# Stethoscope_v1_0.net
KiCad netlist of a schematic drawn in EAGLE
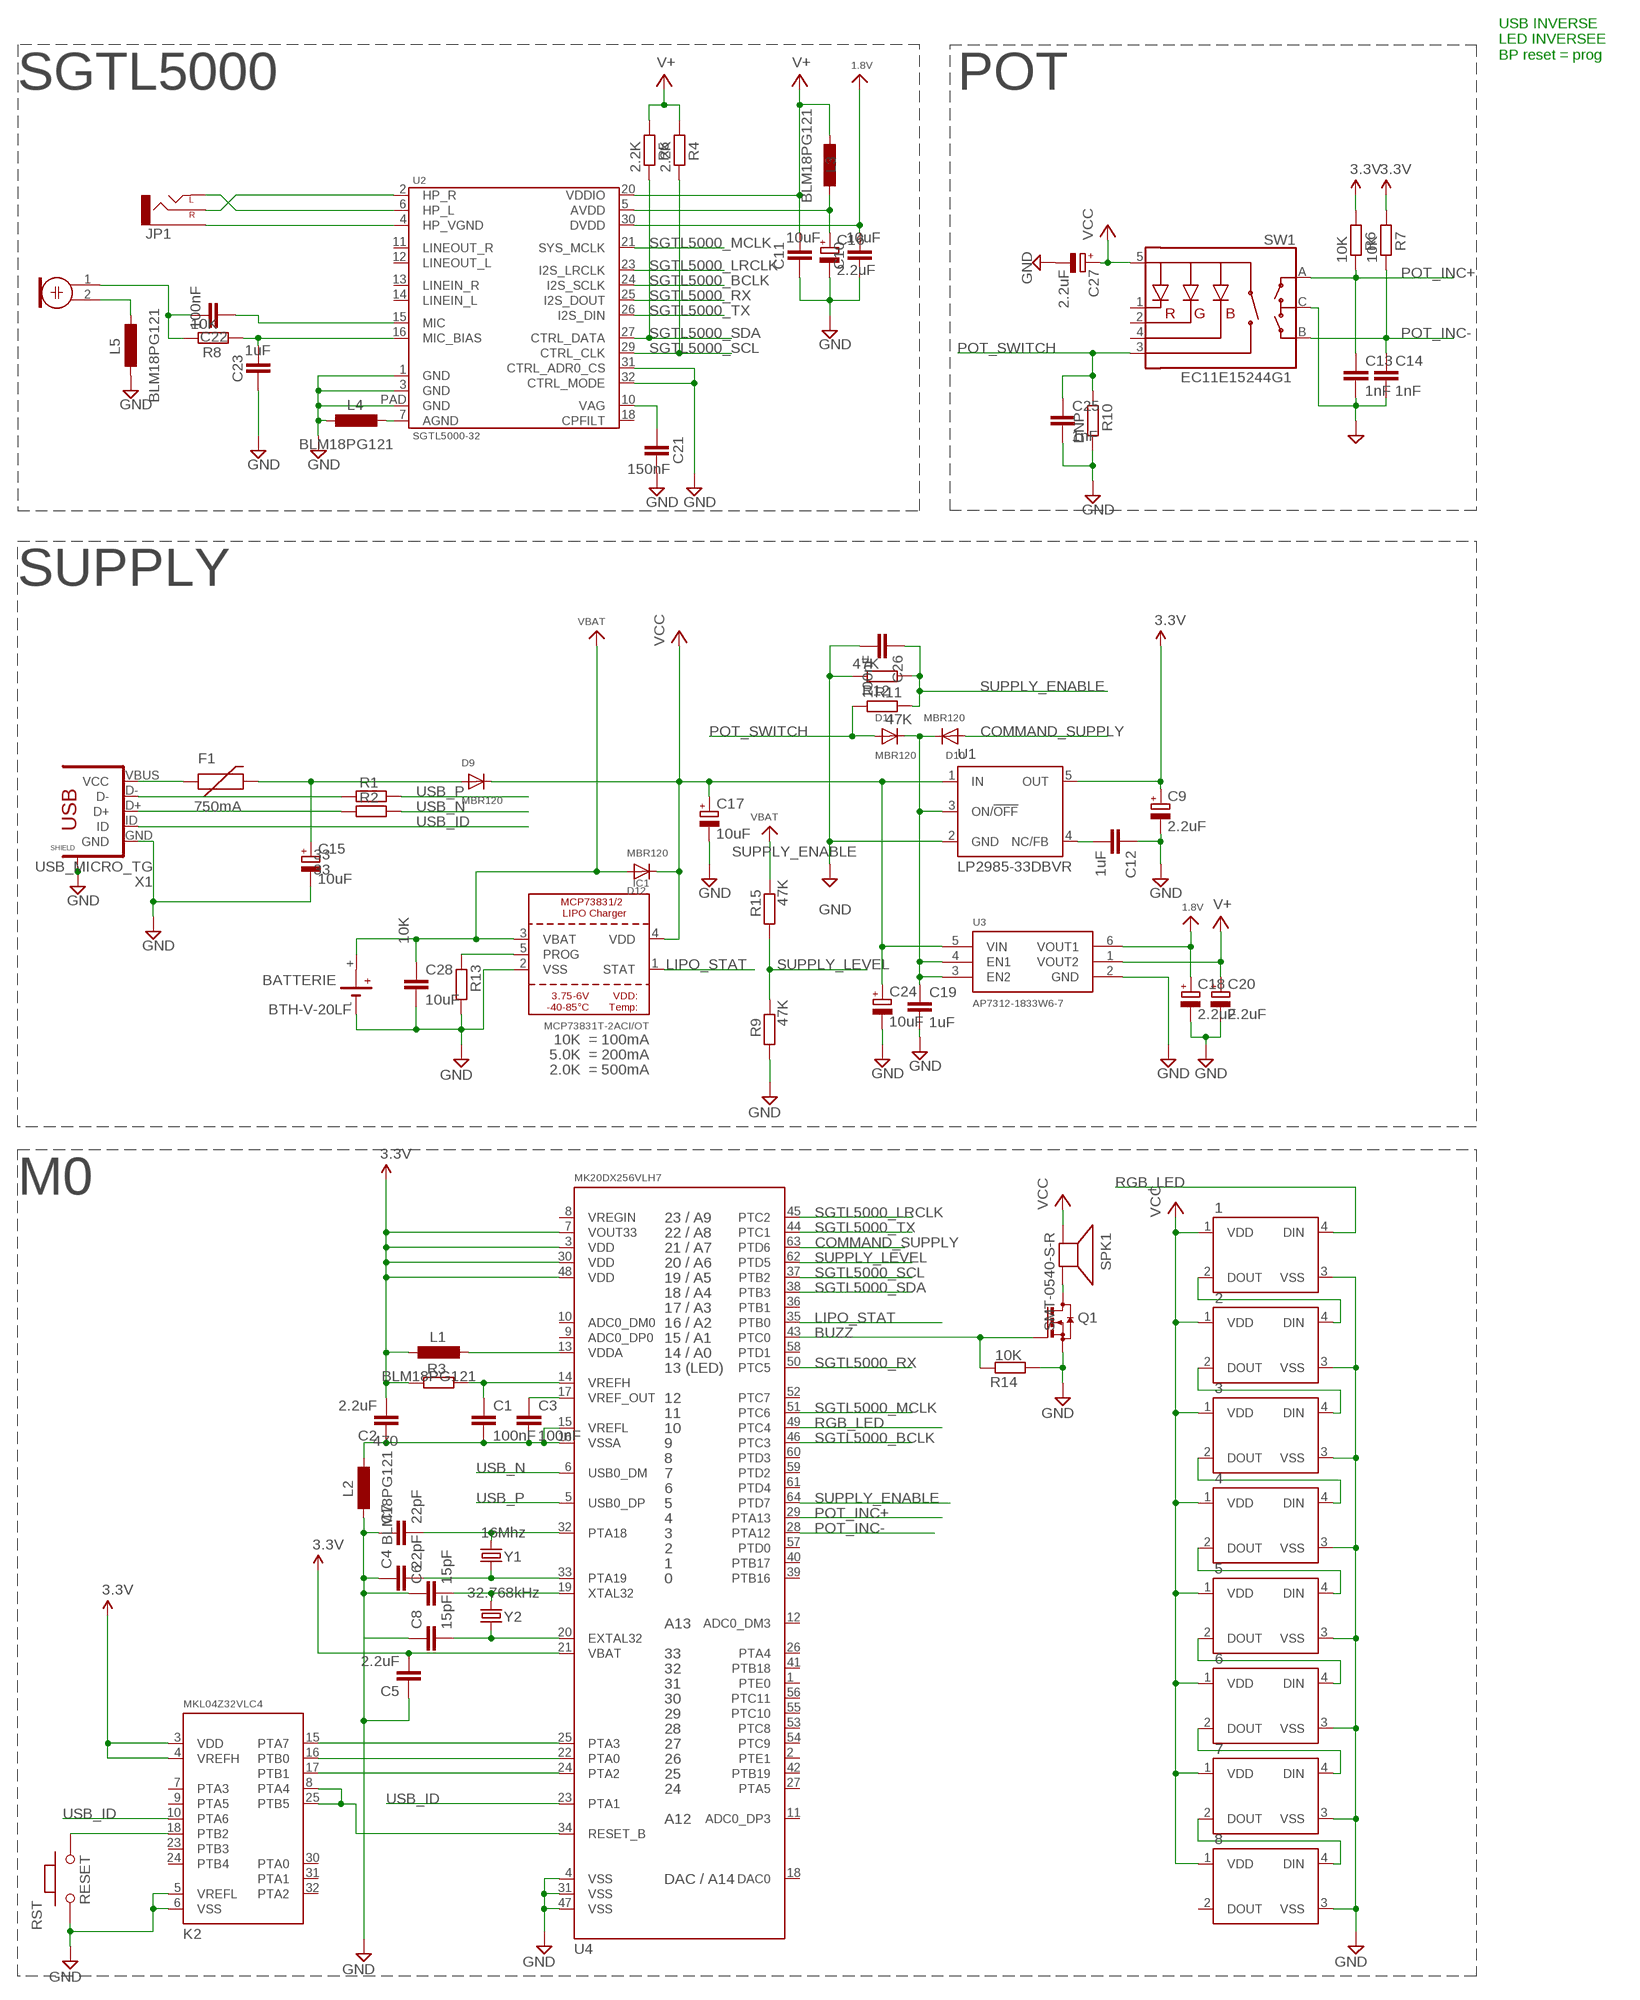
[diagram p0: schematic, sheet 1]

(export (version "E")
  (design (tool "Eeschema 10.0.6"))
  (components
    (comp (ref "1")
      (value "WS2812B")
      (footprint "eagle-import:WS2812B")
      (libsource (lib "eagle-import") (part "WS2812B"))
    )
    (comp (ref "2")
      (value "WS2812B")
      (footprint "eagle-import:WS2812B")
      (libsource (lib "eagle-import") (part "WS2812B"))
    )
    (comp (ref "3")
      (value "WS2812B")
      (footprint "eagle-import:WS2812B")
      (libsource (lib "eagle-import") (part "WS2812B"))
    )
    (comp (ref "4")
      (value "WS2812B")
      (footprint "eagle-import:WS2812B")
      (libsource (lib "eagle-import") (part "WS2812B"))
    )
    (comp (ref "5")
      (value "WS2812B")
      (footprint "eagle-import:WS2812B")
      (libsource (lib "eagle-import") (part "WS2812B"))
    )
    (comp (ref "6")
      (value "WS2812B")
      (footprint "eagle-import:WS2812B")
      (libsource (lib "eagle-import") (part "WS2812B"))
    )
    (comp (ref "7")
      (value "WS2812B")
      (footprint "eagle-import:WS2812B")
      (libsource (lib "eagle-import") (part "WS2812B"))
    )
    (comp (ref "8")
      (value "WS2812B")
      (footprint "eagle-import:WS2812B")
      (libsource (lib "eagle-import") (part "WS2812B"))
    )
    (comp (ref "BATTERIE")
      (value "BTH-V-20LF")
      (footprint "eagle-import:3V_BAT_HOLDER")
      (libsource (lib "eagle-import") (part "B1"))
    )
    (comp (ref "C1")
      (value "100nF")
      (footprint "eagle-import:C0603")
      (libsource (lib "eagle-import") (part "C-EUC0603"))
    )
    (comp (ref "C2")
      (value "2.2uF")
      (footprint "eagle-import:C0603")
      (libsource (lib "eagle-import") (part "C-EUC0603"))
    )
    (comp (ref "C3")
      (value "100nF")
      (footprint "eagle-import:C0603")
      (libsource (lib "eagle-import") (part "C-EUC0603"))
    )
    (comp (ref "C4")
      (value "22pF")
      (footprint "eagle-import:C0603")
      (libsource (lib "eagle-import") (part "C-EUC0603"))
    )
    (comp (ref "C5")
      (value "2.2uF")
      (footprint "eagle-import:C0603")
      (libsource (lib "eagle-import") (part "C-EUC0603"))
    )
    (comp (ref "C6")
      (value "15pF")
      (footprint "eagle-import:C0603")
      (libsource (lib "eagle-import") (part "C-EUC0603"))
    )
    (comp (ref "C7")
      (value "22pF")
      (footprint "eagle-import:C0603")
      (libsource (lib "eagle-import") (part "C-EUC0603"))
    )
    (comp (ref "C8")
      (value "15pF")
      (footprint "eagle-import:C0603")
      (libsource (lib "eagle-import") (part "C-EUC0603"))
    )
    (comp (ref "C9")
      (value "2.2uF")
      (footprint "eagle-import:C0805POL")
      (libsource (lib "eagle-import") (part "CPOL-EUC0805POL"))
    )
    (comp (ref "C10")
      (value "10uF")
      (footprint "eagle-import:C0805")
      (libsource (lib "eagle-import") (part "C-EUC0805"))
    )
    (comp (ref "C11")
      (value "10uF")
      (footprint "eagle-import:C0805")
      (libsource (lib "eagle-import") (part "C-EUC0805"))
    )
    (comp (ref "C12")
      (value "1uF")
      (footprint "eagle-import:C0603")
      (libsource (lib "eagle-import") (part "C-EUC0603"))
    )
    (comp (ref "C13")
      (value "1nF")
      (footprint "eagle-import:C0603")
      (libsource (lib "eagle-import") (part "C-EUC0603"))
    )
    (comp (ref "C14")
      (value "1nF")
      (footprint "eagle-import:C0603")
      (libsource (lib "eagle-import") (part "C-EUC0603"))
    )
    (comp (ref "C15")
      (value "10uF")
      (footprint "eagle-import:C0805POL")
      (libsource (lib "eagle-import") (part "CPOL-EUC0805POL"))
    )
    (comp (ref "C16")
      (value "2.2uF")
      (footprint "eagle-import:C0805POL")
      (libsource (lib "eagle-import") (part "CPOL-EUC0805POL"))
    )
    (comp (ref "C17")
      (value "10uF")
      (footprint "eagle-import:C0805POL")
      (libsource (lib "eagle-import") (part "CPOL-EUC0805POL"))
    )
    (comp (ref "C18")
      (value "2.2uF")
      (footprint "eagle-import:C0805POL")
      (libsource (lib "eagle-import") (part "CPOL-EUC0805POL"))
    )
    (comp (ref "C19")
      (value "1uF")
      (footprint "eagle-import:C0603")
      (libsource (lib "eagle-import") (part "C-EUC0603"))
    )
    (comp (ref "C20")
      (value "2.2uF")
      (footprint "eagle-import:C0805POL")
      (libsource (lib "eagle-import") (part "CPOL-EUC0805POL"))
    )
    (comp (ref "C21")
      (value "150nF")
      (footprint "eagle-import:C0805")
      (libsource (lib "eagle-import") (part "C-EUC0805"))
    )
    (comp (ref "C22")
      (value "100nF")
      (footprint "eagle-import:C0805")
      (libsource (lib "eagle-import") (part "C-EUC0805"))
    )
    (comp (ref "C23")
      (value "1uF")
      (footprint "eagle-import:C0805")
      (libsource (lib "eagle-import") (part "C-EUC0805"))
    )
    (comp (ref "C24")
      (value "10uF")
      (footprint "eagle-import:C0805POL")
      (libsource (lib "eagle-import") (part "CPOL-EUC0805POL"))
    )
    (comp (ref "C25")
      (value "1nF")
      (footprint "eagle-import:C0603")
      (libsource (lib "eagle-import") (part "C-EUC0603"))
    )
    (comp (ref "C26")
      (value "100nF")
      (footprint "eagle-import:C0603")
      (libsource (lib "eagle-import") (part "C-EUC0603"))
    )
    (comp (ref "C27")
      (value "2.2uF")
      (footprint "eagle-import:C0805POL")
      (libsource (lib "eagle-import") (part "CPOL-EUC0805POL"))
    )
    (comp (ref "C28")
      (value "10uF")
      (footprint "eagle-import:C1206")
      (libsource (lib "eagle-import") (part "resistor_C-EUC1206"))
    )
    (comp (ref "D9")
      (value "MBR120")
      (footprint "eagle-import:SOD-323F")
      (libsource (lib "eagle-import") (part "DIODESOD-323F"))
    )
    (comp (ref "D10")
      (value "MBR120")
      (footprint "eagle-import:SOD-323F")
      (libsource (lib "eagle-import") (part "DIODESOD-323F"))
    )
    (comp (ref "D11")
      (value "MBR120")
      (footprint "eagle-import:SOD-323F")
      (libsource (lib "eagle-import") (part "DIODESOD-323F"))
    )
    (comp (ref "D12")
      (value "MBR120")
      (footprint "eagle-import:SOD-323F")
      (libsource (lib "eagle-import") (part "DIODESOD-323F"))
    )
    (comp (ref "F1")
      (value "750mA")
      (footprint "eagle-import:0603")
      (libsource (lib "eagle-import") (part "PTC0603"))
    )
    (comp (ref "IC1")
      (value "MCP73831T-2ACI/OT")
      (footprint "eagle-import:SOT23-5")
      (libsource (lib "eagle-import") (part "MCP73831/2"))
    )
    (comp (ref "JP1")
      (value "AUDIO-JACK1:1")
      (footprint "eagle-import:STEREOJACK2.5MM")
      (libsource (lib "eagle-import") (part "AUDIO-JACK1{colon}1"))
    )
    (comp (ref "K2")
      (value "MKL04Z32VLC4")
      (footprint "eagle-import:LQFP32-08")
      (fields (field (name "MF") "PJRC") (field (name "MPN") "IC_MKL04Z32_TQFP32"))
      (libsource (lib "eagle-import") (part "MKL04Z32VLC4"))
    )
    (comp (ref "L1")
      (value "BLM18PG121")
      (footprint "eagle-import:L0603")
      (libsource (lib "eagle-import") (part "L-EUL0603"))
    )
    (comp (ref "L2")
      (value "BLM18PG121")
      (footprint "eagle-import:L0603")
      (libsource (lib "eagle-import") (part "L-EUL0603"))
    )
    (comp (ref "L3")
      (value "BLM18PG121")
      (footprint "eagle-import:L0603")
      (libsource (lib "eagle-import") (part "L-EUL0603"))
    )
    (comp (ref "L4")
      (value "BLM18PG121")
      (footprint "eagle-import:L0603")
      (libsource (lib "eagle-import") (part "L-EUL0603"))
    )
    (comp (ref "L5")
      (value "BLM18PG121")
      (footprint "eagle-import:L0603")
      (libsource (lib "eagle-import") (part "L-EUL0603"))
    )
    (comp (ref "M1")
      (value "ELECTRET_MICROPHON-F6050AP")
      (footprint "eagle-import:F6050AP")
      (libsource (lib "eagle-import") (part "ELECTRET_MICROPHON-F6050AP"))
    )
    (comp (ref "Q1")
      (value "BSS123")
      (footprint "eagle-import:SOT23")
      (libsource (lib "eagle-import") (part "BSS123"))
    )
    (comp (ref "R1")
      (value "33")
      (footprint "eagle-import:R0603")
      (libsource (lib "eagle-import") (part "resistor_R-EU_R0603"))
    )
    (comp (ref "R2")
      (value "33")
      (footprint "eagle-import:R0603")
      (libsource (lib "eagle-import") (part "resistor_R-EU_R0603"))
    )
    (comp (ref "R3")
      (value "470")
      (footprint "eagle-import:R0603")
      (libsource (lib "eagle-import") (part "resistor_R-EU_R0603"))
    )
    (comp (ref "R4")
      (value "2.2K")
      (footprint "eagle-import:R0603")
      (libsource (lib "eagle-import") (part "R-EU_R0603"))
    )
    (comp (ref "R5")
      (value "2.2K")
      (footprint "eagle-import:R0603")
      (libsource (lib "eagle-import") (part "R-EU_R0603"))
    )
    (comp (ref "R6")
      (value "10K")
      (footprint "eagle-import:R0603")
      (libsource (lib "eagle-import") (part "R-EU_R0603"))
    )
    (comp (ref "R7")
      (value "10K")
      (footprint "eagle-import:R0603")
      (libsource (lib "eagle-import") (part "R-EU_R0603"))
    )
    (comp (ref "R8")
      (value "10K")
      (footprint "eagle-import:R0603")
      (libsource (lib "eagle-import") (part "R-EU_R0603"))
    )
    (comp (ref "R9")
      (value "47K")
      (footprint "eagle-import:R0603")
      (libsource (lib "eagle-import") (part "resistor_R-EU_R0603"))
    )
    (comp (ref "R10")
      (value "DNP")
      (footprint "eagle-import:R0603")
      (libsource (lib "eagle-import") (part "R-EU_R0603"))
    )
    (comp (ref "R11")
      (value "47K")
      (footprint "eagle-import:R0603")
      (libsource (lib "eagle-import") (part "resistor_R-EU_R0603"))
    )
    (comp (ref "R12")
      (value "47K")
      (footprint "eagle-import:R0603")
      (libsource (lib "eagle-import") (part "resistor_R-EU_R0603"))
    )
    (comp (ref "R13")
      (value "10K")
      (footprint "eagle-import:R0603")
      (libsource (lib "eagle-import") (part "resistor_R-EU_R0603"))
    )
    (comp (ref "R14")
      (value "10K")
      (footprint "eagle-import:R0603")
      (libsource (lib "eagle-import") (part "R-EU_R0603"))
    )
    (comp (ref "R15")
      (value "47K")
      (footprint "eagle-import:R0603")
      (libsource (lib "eagle-import") (part "resistor_R-EU_R0603"))
    )
    (comp (ref "RST")
      (value "RESET")
      (footprint "eagle-import:157SW")
      (libsource (lib "eagle-import") (part "PB157"))
    )
    (comp (ref "SPK1")
      (value "SMT-0540-S-R")
      (footprint "eagle-import:SMT-0540-S-R")
      (libsource (lib "eagle-import") (part "SMT-0540-S-R"))
    )
    (comp (ref "SW1")
      (value "EC11E15244G1")
      (footprint "eagle-import:ENCODER_LED_3_KIT")
      (libsource (lib "eagle-import") (part "ENCODER_RGB_CAKIT"))
    )
    (comp (ref "U1")
      (value "LP2985-33DBVR")
      (footprint "eagle-import:SOT23-DBV")
      (libsource (lib "eagle-import") (part "LP2985-XXDBVR33"))
    )
    (comp (ref "U2")
      (value "SGTL5000-32")
      (footprint "eagle-import:QFN-32-5MM")
      (libsource (lib "eagle-import") (part "SGTL5000-32"))
    )
    (comp (ref "U3")
      (value "AP7312-1833W6-7")
      (footprint "eagle-import:SOT23-6")
      (libsource (lib "eagle-import") (part "VREG_SOT23-6_DUALAP7312"))
    )
    (comp (ref "U4")
      (value "MK20DX256VLH7")
      (footprint "eagle-import:LQFP64-05")
      (fields (field (name "MF") "NXP"))
      (libsource (lib "eagle-import") (part "MK20DX256VLH7"))
    )
    (comp (ref "X1")
      (value "USB_MICRO_TG")
      (footprint "eagle-import:USB_MICRO_TG")
      (libsource (lib "eagle-import") (part "USB_MICRO_TG"))
    )
    (comp (ref "Y1")
      (value "16Mhz")
      (footprint "eagle-import:CRYSTAL-SMD-3.2X1.5MM")
      (libsource (lib "eagle-import") (part "CRYSTAL3.2X1.5MM"))
    )
    (comp (ref "Y2")
      (value "32.768kHz")
      (footprint "eagle-import:CRYSTAL-SMD-3.2X1.5MM")
      (libsource (lib "eagle-import") (part "CRYSTAL3.2X1.5MM"))
    )
  )
  (nets
    (net (code "1") (name "/BUZZ") (class "Default")
      (node (ref "Q1") (pin "1") (pinfunction "G_1") (pintype "passive"))
      (node (ref "R14") (pin "2") (pinfunction "2_2") (pintype "passive"))
      (node (ref "U4") (pin "43") (pinfunction "PTC0_43") (pintype "bidirectional"))
    )
    (net (code "2") (name "/COMMAND_SUPPLY") (class "Default")
      (node (ref "D10") (pin "A") (pinfunction "A_A") (pintype "passive"))
      (node (ref "U4") (pin "63") (pinfunction "PTD6_63") (pintype "bidirectional"))
    )
    (net (code "3") (name "/LIPO_STAT") (class "Default")
      (node (ref "IC1") (pin "1") (pinfunction "STAT_1") (pintype "output"))
      (node (ref "U4") (pin "35") (pinfunction "PTB0_35") (pintype "bidirectional"))
    )
    (net (code "4") (name "/POT_INC+") (class "Default")
      (node (ref "C13") (pin "1") (pinfunction "1_1") (pintype "passive"))
      (node (ref "R6") (pin "1") (pinfunction "1_1") (pintype "passive"))
      (node (ref "SW1") (pin "A") (pinfunction "A_A") (pintype "bidirectional"))
      (node (ref "U4") (pin "29") (pinfunction "PTA13_29") (pintype "bidirectional"))
    )
    (net (code "5") (name "/POT_INC-") (class "Default")
      (node (ref "C14") (pin "1") (pinfunction "1_1") (pintype "passive"))
      (node (ref "R7") (pin "1") (pinfunction "1_1") (pintype "passive"))
      (node (ref "SW1") (pin "B") (pinfunction "B_B") (pintype "bidirectional"))
      (node (ref "U4") (pin "28") (pinfunction "PTA12_28") (pintype "bidirectional"))
    )
    (net (code "6") (name "/POT_SWITCH") (class "Default")
      (node (ref "C25") (pin "1") (pinfunction "1_1") (pintype "passive"))
      (node (ref "D11") (pin "A") (pinfunction "A_A") (pintype "passive"))
      (node (ref "R10") (pin "2") (pinfunction "2_2") (pintype "passive"))
      (node (ref "R11") (pin "1") (pinfunction "1_1") (pintype "passive"))
      (node (ref "SW1") (pin "3") (pinfunction "SW_3") (pintype "passive"))
    )
    (net (code "7") (name "/RGB_LED") (class "Default")
      (node (ref "1") (pin "4") (pinfunction "DIN_4") (pintype "input"))
      (node (ref "U4") (pin "49") (pinfunction "PTC4_49") (pintype "bidirectional"))
    )
    (net (code "8") (name "/SGTL5000_BCLK") (class "Default")
      (node (ref "U2") (pin "24") (pinfunction "I2S_SCLK_24") (pintype "bidirectional"))
      (node (ref "U4") (pin "46") (pinfunction "PTC3_46") (pintype "bidirectional"))
    )
    (net (code "9") (name "/SGTL5000_LRCLK") (class "Default")
      (node (ref "U2") (pin "23") (pinfunction "I2S_LRCLK_23") (pintype "bidirectional"))
      (node (ref "U4") (pin "45") (pinfunction "PTC2_45") (pintype "bidirectional"))
    )
    (net (code "10") (name "/SGTL5000_MCLK") (class "Default")
      (node (ref "U2") (pin "21") (pinfunction "SYS_MCLK_21") (pintype "bidirectional"))
      (node (ref "U4") (pin "51") (pinfunction "PTC6_51") (pintype "bidirectional"))
    )
    (net (code "11") (name "/SGTL5000_RX") (class "Default")
      (node (ref "U2") (pin "25") (pinfunction "I2S_DOUT_25") (pintype "bidirectional"))
      (node (ref "U4") (pin "50") (pinfunction "PTC5_50") (pintype "bidirectional"))
    )
    (net (code "12") (name "/SGTL5000_SCL") (class "Default")
      (node (ref "R4") (pin "1") (pinfunction "1_1") (pintype "passive"))
      (node (ref "U2") (pin "29") (pinfunction "CTRL_CLK_29") (pintype "bidirectional"))
      (node (ref "U4") (pin "37") (pinfunction "PTB2_37") (pintype "bidirectional"))
    )
    (net (code "13") (name "/SGTL5000_SDA") (class "Default")
      (node (ref "R5") (pin "1") (pinfunction "1_1") (pintype "passive"))
      (node (ref "U2") (pin "27") (pinfunction "CTRL_DATA_27") (pintype "bidirectional"))
      (node (ref "U4") (pin "38") (pinfunction "PTB3_38") (pintype "bidirectional"))
    )
    (net (code "14") (name "/SGTL5000_TX") (class "Default")
      (node (ref "U2") (pin "26") (pinfunction "I2S_DIN_26") (pintype "bidirectional"))
      (node (ref "U4") (pin "44") (pinfunction "PTC1_44") (pintype "bidirectional"))
    )
    (net (code "15") (name "/SUPPLY_ENABLE") (class "Default")
      (node (ref "C26") (pin "1") (pinfunction "1_1") (pintype "passive"))
      (node (ref "R11") (pin "2") (pinfunction "2_2") (pintype "passive"))
      (node (ref "R12") (pin "1") (pinfunction "1_1") (pintype "passive"))
      (node (ref "U4") (pin "64") (pinfunction "PTD7_64") (pintype "bidirectional"))
    )
    (net (code "16") (name "/SUPPLY_LEVEL") (class "Default")
      (node (ref "R15") (pin "1") (pinfunction "1_1") (pintype "passive"))
      (node (ref "R9") (pin "2") (pinfunction "2_2") (pintype "passive"))
      (node (ref "U4") (pin "62") (pinfunction "PTD5_62") (pintype "bidirectional"))
    )
    (net (code "17") (name "/USB_ID") (class "Default")
      (node (ref "K2") (pin "10") (pinfunction "PTA6_10") (pintype "bidirectional"))
      (node (ref "U4") (pin "23") (pinfunction "PTA1_23") (pintype "bidirectional"))
      (node (ref "X1") (pin "ID") (pinfunction "ID_ID") (pintype "bidirectional"))
    )
    (net (code "18") (name "/USB_N") (class "Default")
      (node (ref "R2") (pin "1") (pinfunction "1_1") (pintype "passive"))
      (node (ref "U4") (pin "6") (pinfunction "USB0_DM_6") (pintype "bidirectional"))
    )
    (net (code "19") (name "/USB_P") (class "Default")
      (node (ref "R1") (pin "1") (pinfunction "1_1") (pintype "passive"))
      (node (ref "U4") (pin "5") (pinfunction "USB0_DP_5") (pintype "bidirectional"))
    )
    (net (code "20") (name "1.8V") (class "Default")
      (node (ref "C10") (pin "2") (pinfunction "2_2") (pintype "passive"))
      (node (ref "C18") (pin "SMD+") (pinfunction "+_SMD+") (pintype "passive"))
      (node (ref "U2") (pin "30") (pinfunction "DVDD_30") (pintype "bidirectional"))
      (node (ref "U3") (pin "6") (pinfunction "VOUT1_6") (pintype "bidirectional"))
    )
    (net (code "21") (name "3.3V") (class "Default")
      (node (ref "C2") (pin "2") (pinfunction "2_2") (pintype "passive"))
      (node (ref "C5") (pin "2") (pinfunction "2_2") (pintype "passive"))
      (node (ref "C9") (pin "SMD+") (pinfunction "+_SMD+") (pintype "passive"))
      (node (ref "K2") (pin "3") (pinfunction "VDD_3") (pintype "bidirectional"))
      (node (ref "K2") (pin "4") (pinfunction "VREFH_4") (pintype "bidirectional"))
      (node (ref "L1") (pin "2") (pinfunction "2_2") (pintype "passive"))
      (node (ref "R3") (pin "2") (pinfunction "2_2") (pintype "passive"))
      (node (ref "R6") (pin "2") (pinfunction "2_2") (pintype "passive"))
      (node (ref "R7") (pin "2") (pinfunction "2_2") (pintype "passive"))
      (node (ref "U1") (pin "5") (pinfunction "OUT_5") (pintype "passive"))
      (node (ref "U4") (pin "21") (pinfunction "VBAT_21") (pintype "bidirectional"))
      (node (ref "U4") (pin "3") (pinfunction "VDD_3") (pintype "bidirectional"))
      (node (ref "U4") (pin "30") (pinfunction "VDD_30") (pintype "bidirectional"))
      (node (ref "U4") (pin "48") (pinfunction "VDD_48") (pintype "bidirectional"))
      (node (ref "U4") (pin "7") (pinfunction "VOUT33_7") (pintype "bidirectional"))
    )
    (net (code "22") (name "GND") (class "Default")
      (node (ref "1") (pin "3") (pinfunction "VSS_3") (pintype "power_in"))
      (node (ref "2") (pin "3") (pinfunction "VSS_3") (pintype "power_in"))
      (node (ref "3") (pin "3") (pinfunction "VSS_3") (pintype "power_in"))
      (node (ref "4") (pin "3") (pinfunction "VSS_3") (pintype "power_in"))
      (node (ref "5") (pin "3") (pinfunction "VSS_3") (pintype "power_in"))
      (node (ref "6") (pin "3") (pinfunction "VSS_3") (pintype "power_in"))
      (node (ref "7") (pin "3") (pinfunction "VSS_3") (pintype "power_in"))
      (node (ref "8") (pin "3") (pinfunction "VSS_3") (pintype "power_in"))
      (node (ref "BATTERIE") (pin "-") (pinfunction "-_-") (pintype "passive"))
      (node (ref "C10") (pin "1") (pinfunction "1_1") (pintype "passive"))
      (node (ref "C11") (pin "1") (pinfunction "1_1") (pintype "passive"))
      (node (ref "C12") (pin "1") (pinfunction "1_1") (pintype "passive"))
      (node (ref "C13") (pin "2") (pinfunction "2_2") (pintype "passive"))
      (node (ref "C14") (pin "2") (pinfunction "2_2") (pintype "passive"))
      (node (ref "C15") (pin "SMD-") (pinfunction "-_SMD-") (pintype "passive"))
      (node (ref "C16") (pin "SMD-") (pinfunction "-_SMD-") (pintype "passive"))
      (node (ref "C17") (pin "SMD-") (pinfunction "-_SMD-") (pintype "passive"))
      (node (ref "C18") (pin "SMD-") (pinfunction "-_SMD-") (pintype "passive"))
      (node (ref "C19") (pin "2") (pinfunction "2_2") (pintype "passive"))
      (node (ref "C20") (pin "SMD-") (pinfunction "-_SMD-") (pintype "passive"))
      (node (ref "C21") (pin "2") (pinfunction "2_2") (pintype "passive"))
      (node (ref "C23") (pin "1") (pinfunction "1_1") (pintype "passive"))
      (node (ref "C24") (pin "SMD-") (pinfunction "-_SMD-") (pintype "passive"))
      (node (ref "C25") (pin "2") (pinfunction "2_2") (pintype "passive"))
      (node (ref "C26") (pin "2") (pinfunction "2_2") (pintype "passive"))
      (node (ref "C27") (pin "SMD-") (pinfunction "-_SMD-") (pintype "passive"))
      (node (ref "C28") (pin "2") (pinfunction "2_2") (pintype "passive"))
      (node (ref "C4") (pin "1") (pinfunction "1_1") (pintype "passive"))
      (node (ref "C5") (pin "1") (pinfunction "1_1") (pintype "passive"))
      (node (ref "C6") (pin "1") (pinfunction "1_1") (pintype "passive"))
      (node (ref "C7") (pin "1") (pinfunction "1_1") (pintype "passive"))
      (node (ref "C8") (pin "1") (pinfunction "1_1") (pintype "passive"))
      (node (ref "C9") (pin "SMD-") (pinfunction "-_SMD-") (pintype "passive"))
      (node (ref "IC1") (pin "2") (pinfunction "VSS_2") (pintype "power_in"))
      (node (ref "K2") (pin "5") (pinfunction "VREFL_5") (pintype "bidirectional"))
      (node (ref "K2") (pin "6") (pinfunction "VSS_6") (pintype "bidirectional"))
      (node (ref "L2") (pin "2") (pinfunction "2_2") (pintype "passive"))
      (node (ref "L4") (pin "2") (pinfunction "2_2") (pintype "passive"))
      (node (ref "L5") (pin "2") (pinfunction "2_2") (pintype "passive"))
      (node (ref "Q1") (pin "2") (pinfunction "S_2") (pintype "passive"))
      (node (ref "R10") (pin "1") (pinfunction "1_1") (pintype "passive"))
      (node (ref "R12") (pin "2") (pinfunction "2_2") (pintype "passive"))
      (node (ref "R13") (pin "1") (pinfunction "1_1") (pintype "passive"))
      (node (ref "R14") (pin "1") (pinfunction "1_1") (pintype "passive"))
      (node (ref "R9") (pin "1") (pinfunction "1_1") (pintype "passive"))
      (node (ref "RST") (pin "1") (pinfunction "1_1") (pintype "passive"))
      (node (ref "SW1") (pin "C") (pinfunction "C_C") (pintype "bidirectional"))
      (node (ref "U1") (pin "2") (pinfunction "GND_2") (pintype "power_in"))
      (node (ref "U2") (pin "1") (pinfunction "GND_1") (pintype "bidirectional"))
      (node (ref "U2") (pin "3") (pinfunction "GND_3") (pintype "bidirectional"))
      (node (ref "U2") (pin "31") (pinfunction "CTRL_ADR0_CS_31") (pintype "bidirectional"))
      (node (ref "U2") (pin "32") (pinfunction "CTRL_MODE_32") (pintype "bidirectional"))
      (node (ref "U2") (pin "PAD") (pinfunction "GND_PAD") (pintype "bidirectional"))
      (node (ref "U3") (pin "2") (pinfunction "GND_2") (pintype "bidirectional"))
      (node (ref "U4") (pin "31") (pinfunction "VSS_31") (pintype "bidirectional"))
      (node (ref "U4") (pin "4") (pinfunction "VSS_4") (pintype "bidirectional"))
      (node (ref "U4") (pin "47") (pinfunction "VSS_47") (pintype "bidirectional"))
      (node (ref "X1") (pin "GND") (pinfunction "GND_GND") (pintype "bidirectional"))
      (node (ref "X1") (pin "SHIELD") (pinfunction "SHIELD_SHIELD") (pintype "bidirectional"))
      (node (ref "X1") (pin "SHIELD2") (pinfunction "SHIELD1_SHIELD2") (pintype "bidirectional"))
      (node (ref "X1") (pin "SHIELD3") (pinfunction "SHIELD2_SHIELD3") (pintype "bidirectional"))
      (node (ref "X1") (pin "SHIELD4") (pinfunction "SHIELD3_SHIELD4") (pintype "bidirectional"))
      (node (ref "X1") (pin "SHIELD5") (pinfunction "SHIELD4_SHIELD5") (pintype "bidirectional"))
      (node (ref "X1") (pin "SHIELD6") (pinfunction "SHIELD5_SHIELD6") (pintype "bidirectional"))
      (node (ref "X1") (pin "SHIELD7") (pinfunction "SHIELD6_SHIELD7") (pintype "bidirectional"))
      (node (ref "X1") (pin "SHIELD8") (pinfunction "SHIELD7_SHIELD8") (pintype "bidirectional"))
    )
    (net (code "23") (name "Net-(1-DOUT)") (class "Default")
      (node (ref "1") (pin "2") (pinfunction "DOUT_2") (pintype "output"))
      (node (ref "2") (pin "4") (pinfunction "DIN_4") (pintype "input"))
    )
    (net (code "24") (name "Net-(2-DOUT)") (class "Default")
      (node (ref "2") (pin "2") (pinfunction "DOUT_2") (pintype "output"))
      (node (ref "3") (pin "4") (pinfunction "DIN_4") (pintype "input"))
    )
    (net (code "25") (name "Net-(3-DOUT)") (class "Default")
      (node (ref "3") (pin "2") (pinfunction "DOUT_2") (pintype "output"))
      (node (ref "4") (pin "4") (pinfunction "DIN_4") (pintype "input"))
    )
    (net (code "26") (name "Net-(4-DOUT)") (class "Default")
      (node (ref "4") (pin "2") (pinfunction "DOUT_2") (pintype "output"))
      (node (ref "5") (pin "4") (pinfunction "DIN_4") (pintype "input"))
    )
    (net (code "27") (name "Net-(5-DOUT)") (class "Default")
      (node (ref "5") (pin "2") (pinfunction "DOUT_2") (pintype "output"))
      (node (ref "6") (pin "4") (pinfunction "DIN_4") (pintype "input"))
    )
    (net (code "28") (name "Net-(6-DOUT)") (class "Default")
      (node (ref "6") (pin "2") (pinfunction "DOUT_2") (pintype "output"))
      (node (ref "7") (pin "4") (pinfunction "DIN_4") (pintype "input"))
    )
    (net (code "29") (name "Net-(7-DOUT)") (class "Default")
      (node (ref "7") (pin "2") (pinfunction "DOUT_2") (pintype "output"))
      (node (ref "8") (pin "4") (pinfunction "DIN_4") (pintype "input"))
    )
    (net (code "30") (name "Net-(C15-+)") (class "Default")
      (node (ref "C15") (pin "SMD+") (pinfunction "+_SMD+") (pintype "passive"))
      (node (ref "D9") (pin "A") (pinfunction "A_A") (pintype "passive"))
      (node (ref "F1") (pin "2") (pinfunction "2_2") (pintype "bidirectional"))
    )
    (net (code "31") (name "Net-(C16-+)") (class "Default")
      (node (ref "C16") (pin "SMD+") (pinfunction "+_SMD+") (pintype "passive"))
      (node (ref "L3") (pin "1") (pinfunction "1_1") (pintype "passive"))
      (node (ref "U2") (pin "5") (pinfunction "AVDD_5") (pintype "bidirectional"))
    )
    (net (code "32") (name "Net-(C22-Pad2)") (class "Default")
      (node (ref "C22") (pin "2") (pinfunction "2_2") (pintype "passive"))
      (node (ref "M1") (pin "1") (pinfunction "1_1") (pintype "passive"))
      (node (ref "R8") (pin "1") (pinfunction "1_1") (pintype "passive"))
    )
    (net (code "33") (name "Net-(IC1-PROG)") (class "Default")
      (node (ref "IC1") (pin "5") (pinfunction "PROG_5") (pintype "input"))
      (node (ref "R13") (pin "2") (pinfunction "2_2") (pintype "passive"))
    )
    (net (code "34") (name "Net-(JP1-LEFT)") (class "Default")
      (node (ref "JP1") (pin "1") (pinfunction "LEFT_1") (pintype "bidirectional"))
      (node (ref "U2") (pin "6") (pinfunction "HP_L_6") (pintype "bidirectional"))
    )
    (net (code "35") (name "Net-(JP1-RIGHT)") (class "Default")
      (node (ref "JP1") (pin "4") (pinfunction "RIGHT_4") (pintype "bidirectional"))
      (node (ref "U2") (pin "2") (pinfunction "HP_R_2") (pintype "bidirectional"))
    )
    (net (code "36") (name "Net-(JP1-SLEEVE)") (class "Default")
      (node (ref "JP1") (pin "5") (pinfunction "SLEEVE_5") (pintype "bidirectional"))
      (node (ref "U2") (pin "4") (pinfunction "HP_VGND_4") (pintype "bidirectional"))
    )
    (net (code "37") (name "Net-(K2-PTA4)") (class "Default")
      (node (ref "K2") (pin "25") (pinfunction "PTB5_25") (pintype "bidirectional"))
      (node (ref "K2") (pin "8") (pinfunction "PTA4_8") (pintype "bidirectional"))
      (node (ref "U4") (pin "34") (pinfunction "RESET_B_34") (pintype "bidirectional"))
    )
    (net (code "38") (name "Net-(K2-PTA7)") (class "Default")
      (node (ref "K2") (pin "15") (pinfunction "PTA7_15") (pintype "bidirectional"))
      (node (ref "U4") (pin "25") (pinfunction "PTA3_25") (pintype "bidirectional"))
    )
    (net (code "39") (name "Net-(K2-PTB0)") (class "Default")
      (node (ref "K2") (pin "16") (pinfunction "PTB0_16") (pintype "bidirectional"))
      (node (ref "U4") (pin "22") (pinfunction "PTA0_22") (pintype "bidirectional"))
    )
    (net (code "40") (name "Net-(K2-PTB1)") (class "Default")
      (node (ref "K2") (pin "17") (pinfunction "PTB1_17") (pintype "bidirectional"))
      (node (ref "U4") (pin "24") (pinfunction "PTA2_24") (pintype "bidirectional"))
    )
    (net (code "41") (name "Net-(K2-PTB2)") (class "Default")
      (node (ref "K2") (pin "18") (pinfunction "PTB2_18") (pintype "bidirectional"))
      (node (ref "RST") (pin "2") (pinfunction "2_2") (pintype "passive"))
    )
    (net (code "42") (name "Net-(L5-Pad1)") (class "Default")
      (node (ref "L5") (pin "1") (pinfunction "1_1") (pintype "passive"))
      (node (ref "M1") (pin "2") (pinfunction "2_2") (pintype "passive"))
    )
    (net (code "43") (name "Net-(Q1-D)") (class "Default")
      (node (ref "Q1") (pin "3") (pinfunction "D_3") (pintype "passive"))
      (node (ref "SPK1") (pin "+") (pinfunction "-_+") (pintype "passive"))
    )
    (net (code "44") (name "Net-(R1-Pad2)") (class "Default")
      (node (ref "R1") (pin "2") (pinfunction "2_2") (pintype "passive"))
      (node (ref "X1") (pin "D-") (pinfunction "D-_D-") (pintype "bidirectional"))
    )
    (net (code "45") (name "Net-(R2-Pad2)") (class "Default")
      (node (ref "R2") (pin "2") (pinfunction "2_2") (pintype "passive"))
      (node (ref "X1") (pin "D+") (pinfunction "D+_D+") (pintype "bidirectional"))
    )
    (net (code "46") (name "Net-(U1-NC{slash}FB)") (class "Default")
      (node (ref "C12") (pin "2") (pinfunction "2_2") (pintype "passive"))
      (node (ref "U1") (pin "4") (pinfunction "NC/FB_4") (pintype "passive"))
    )
    (net (code "47") (name "Net-(U1-ON{slash}~{OFF})") (class "Default")
      (node (ref "C19") (pin "1") (pinfunction "1_1") (pintype "passive"))
      (node (ref "D10") (pin "C") (pinfunction "C_C") (pintype "passive"))
      (node (ref "D11") (pin "C") (pinfunction "C_C") (pintype "passive"))
      (node (ref "U1") (pin "3") (pinfunction "ON/~{OFF}_3") (pintype "input"))
      (node (ref "U3") (pin "3") (pinfunction "EN2_3") (pintype "bidirectional"))
      (node (ref "U3") (pin "4") (pinfunction "EN1_4") (pintype "bidirectional"))
    )
    (net (code "48") (name "Net-(U2-AGND)") (class "Default")
      (node (ref "L4") (pin "1") (pinfunction "1_1") (pintype "passive"))
      (node (ref "U2") (pin "7") (pinfunction "AGND_7") (pintype "bidirectional"))
    )
    (net (code "49") (name "Net-(U2-MIC)") (class "Default")
      (node (ref "C22") (pin "1") (pinfunction "1_1") (pintype "passive"))
      (node (ref "U2") (pin "15") (pinfunction "MIC_15") (pintype "bidirectional"))
    )
    (net (code "50") (name "Net-(U2-MIC_BIAS)") (class "Default")
      (node (ref "C23") (pin "2") (pinfunction "2_2") (pintype "passive"))
      (node (ref "R8") (pin "2") (pinfunction "2_2") (pintype "passive"))
      (node (ref "U2") (pin "16") (pinfunction "MIC_BIAS_16") (pintype "bidirectional"))
    )
    (net (code "51") (name "Net-(U2-VAG)") (class "Default")
      (node (ref "C21") (pin "1") (pinfunction "1_1") (pintype "passive"))
      (node (ref "U2") (pin "10") (pinfunction "VAG_10") (pintype "bidirectional"))
    )
    (net (code "52") (name "Net-(U4-EXTAL32)") (class "Default")
      (node (ref "C8") (pin "2") (pinfunction "2_2") (pintype "passive"))
      (node (ref "U4") (pin "20") (pinfunction "EXTAL32_20") (pintype "bidirectional"))
      (node (ref "Y2") (pin "P$1") (pinfunction "1_P$1") (pintype "passive"))
    )
    (net (code "53") (name "Net-(U4-PTA18)") (class "Default")
      (node (ref "C7") (pin "2") (pinfunction "2_2") (pintype "passive"))
      (node (ref "U4") (pin "32") (pinfunction "PTA18_32") (pintype "bidirectional"))
      (node (ref "Y1") (pin "P$2") (pinfunction "2_P$2") (pintype "passive"))
    )
    (net (code "54") (name "Net-(U4-PTA19)") (class "Default")
      (node (ref "C4") (pin "2") (pinfunction "2_2") (pintype "passive"))
      (node (ref "U4") (pin "33") (pinfunction "PTA19_33") (pintype "bidirectional"))
      (node (ref "Y1") (pin "P$1") (pinfunction "1_P$1") (pintype "passive"))
    )
    (net (code "55") (name "Net-(U4-VDDA)") (class "Default")
      (node (ref "L1") (pin "1") (pinfunction "1_1") (pintype "passive"))
      (node (ref "U4") (pin "13") (pinfunction "VDDA_13") (pintype "bidirectional"))
    )
    (net (code "56") (name "Net-(U4-VREFH)") (class "Default")
      (node (ref "C1") (pin "1") (pinfunction "1_1") (pintype "passive"))
      (node (ref "R3") (pin "1") (pinfunction "1_1") (pintype "passive"))
      (node (ref "U4") (pin "14") (pinfunction "VREFH_14") (pintype "bidirectional"))
    )
    (net (code "57") (name "Net-(U4-VREFL)") (class "Default")
      (node (ref "C1") (pin "2") (pinfunction "2_2") (pintype "passive"))
      (node (ref "C2") (pin "1") (pinfunction "1_1") (pintype "passive"))
      (node (ref "C3") (pin "2") (pinfunction "2_2") (pintype "passive"))
      (node (ref "L2") (pin "1") (pinfunction "1_1") (pintype "passive"))
      (node (ref "U4") (pin "15") (pinfunction "VREFL_15") (pintype "bidirectional"))
      (node (ref "U4") (pin "16") (pinfunction "VSSA_16") (pintype "bidirectional"))
    )
    (net (code "58") (name "Net-(U4-VREF_OUT)") (class "Default")
      (node (ref "C3") (pin "1") (pinfunction "1_1") (pintype "passive"))
      (node (ref "U4") (pin "17") (pinfunction "VREF_OUT_17") (pintype "bidirectional"))
    )
    (net (code "59") (name "Net-(U4-XTAL32)") (class "Default")
      (node (ref "C6") (pin "2") (pinfunction "2_2") (pintype "passive"))
      (node (ref "U4") (pin "19") (pinfunction "XTAL32_19") (pintype "bidirectional"))
      (node (ref "Y2") (pin "P$2") (pinfunction "2_P$2") (pintype "passive"))
    )
    (net (code "60") (name "Net-(X1-VCC)") (class "Default")
      (node (ref "F1") (pin "1") (pinfunction "1_1") (pintype "bidirectional"))
      (node (ref "X1") (pin "VBUS") (pinfunction "VCC_VBUS") (pintype "bidirectional"))
    )
    (net (code "61") (name "V+") (class "Default")
      (node (ref "C11") (pin "2") (pinfunction "2_2") (pintype "passive"))
      (node (ref "C20") (pin "SMD+") (pinfunction "+_SMD+") (pintype "passive"))
      (node (ref "L3") (pin "2") (pinfunction "2_2") (pintype "passive"))
      (node (ref "R4") (pin "2") (pinfunction "2_2") (pintype "passive"))
      (node (ref "R5") (pin "2") (pinfunction "2_2") (pintype "passive"))
      (node (ref "U2") (pin "20") (pinfunction "VDDIO_20") (pintype "bidirectional"))
      (node (ref "U3") (pin "1") (pinfunction "VOUT2_1") (pintype "bidirectional"))
    )
    (net (code "62") (name "VBAT") (class "Default")
      (node (ref "BATTERIE") (pin "+") (pinfunction "+_+") (pintype "passive"))
      (node (ref "C28") (pin "1") (pinfunction "1_1") (pintype "passive"))
      (node (ref "D12") (pin "A") (pinfunction "A_A") (pintype "passive"))
      (node (ref "IC1") (pin "3") (pinfunction "VBAT_3") (pintype "power_in"))
      (node (ref "R15") (pin "2") (pinfunction "2_2") (pintype "passive"))
    )
    (net (code "63") (name "VCC") (class "Default")
      (node (ref "1") (pin "1") (pinfunction "VDD_1") (pintype "power_in"))
      (node (ref "2") (pin "1") (pinfunction "VDD_1") (pintype "power_in"))
      (node (ref "3") (pin "1") (pinfunction "VDD_1") (pintype "power_in"))
      (node (ref "4") (pin "1") (pinfunction "VDD_1") (pintype "power_in"))
      (node (ref "5") (pin "1") (pinfunction "VDD_1") (pintype "power_in"))
      (node (ref "6") (pin "1") (pinfunction "VDD_1") (pintype "power_in"))
      (node (ref "7") (pin "1") (pinfunction "VDD_1") (pintype "power_in"))
      (node (ref "8") (pin "1") (pinfunction "VDD_1") (pintype "power_in"))
      (node (ref "C17") (pin "SMD+") (pinfunction "+_SMD+") (pintype "passive"))
      (node (ref "C24") (pin "SMD+") (pinfunction "+_SMD+") (pintype "passive"))
      (node (ref "C27") (pin "SMD+") (pinfunction "+_SMD+") (pintype "passive"))
      (node (ref "D12") (pin "C") (pinfunction "C_C") (pintype "passive"))
      (node (ref "D9") (pin "C") (pinfunction "C_C") (pintype "passive"))
      (node (ref "IC1") (pin "4") (pinfunction "VDD_4") (pintype "power_in"))
      (node (ref "SPK1") (pin "-") (pinfunction "+_-") (pintype "passive"))
      (node (ref "SW1") (pin "5") (pinfunction "+_5") (pintype "passive"))
      (node (ref "U1") (pin "1") (pinfunction "IN_1") (pintype "input"))
      (node (ref "U3") (pin "5") (pinfunction "VIN_5") (pintype "bidirectional"))
    )
    (net (code "64") (name "unconnected-(8-DOUT-Pad2)") (class "Default")
      (node (ref "8") (pin "2") (pinfunction "DOUT_2") (pintype "output"))
    )
    (net (code "65") (name "unconnected-(BATTERIE-+-Pad1+)") (class "Default")
      (node (ref "BATTERIE") (pin "1+") (pinfunction "+_1+") (pintype "passive"))
    )
    (net (code "66") (name "unconnected-(K2-PTA0-Pad30)") (class "Default")
      (node (ref "K2") (pin "30") (pinfunction "PTA0_30") (pintype "bidirectional"))
    )
    (net (code "67") (name "unconnected-(K2-PTA1-Pad31)") (class "Default")
      (node (ref "K2") (pin "31") (pinfunction "PTA1_31") (pintype "bidirectional"))
    )
    (net (code "68") (name "unconnected-(K2-PTA2-Pad32)") (class "Default")
      (node (ref "K2") (pin "32") (pinfunction "PTA2_32") (pintype "bidirectional"))
    )
    (net (code "69") (name "unconnected-(K2-PTA3-Pad7)") (class "Default")
      (node (ref "K2") (pin "7") (pinfunction "PTA3_7") (pintype "bidirectional"))
    )
    (net (code "70") (name "unconnected-(K2-PTA5-Pad9)") (class "Default")
      (node (ref "K2") (pin "9") (pinfunction "PTA5_9") (pintype "bidirectional"))
    )
    (net (code "71") (name "unconnected-(K2-PTB3-Pad23)") (class "Default")
      (node (ref "K2") (pin "23") (pinfunction "PTB3_23") (pintype "bidirectional"))
    )
    (net (code "72") (name "unconnected-(K2-PTB4-Pad24)") (class "Default")
      (node (ref "K2") (pin "24") (pinfunction "PTB4_24") (pintype "bidirectional"))
    )
    (net (code "73") (name "unconnected-(SW1--B-Pad4)") (class "Default")
      (node (ref "SW1") (pin "4") (pinfunction "-B_4") (pintype "passive"))
    )
    (net (code "74") (name "unconnected-(SW1--G-Pad2)") (class "Default")
      (node (ref "SW1") (pin "2") (pinfunction "-G_2") (pintype "passive"))
    )
    (net (code "75") (name "unconnected-(SW1--R-Pad1)") (class "Default")
      (node (ref "SW1") (pin "1") (pinfunction "-R_1") (pintype "passive"))
    )
    (net (code "76") (name "unconnected-(U2-CPFILT-Pad18)") (class "Default")
      (node (ref "U2") (pin "18") (pinfunction "CPFILT_18") (pintype "bidirectional"))
    )
    (net (code "77") (name "unconnected-(U2-LINEIN_L-Pad14)") (class "Default")
      (node (ref "U2") (pin "14") (pinfunction "LINEIN_L_14") (pintype "bidirectional"))
    )
    (net (code "78") (name "unconnected-(U2-LINEIN_R-Pad13)") (class "Default")
      (node (ref "U2") (pin "13") (pinfunction "LINEIN_R_13") (pintype "bidirectional"))
    )
    (net (code "79") (name "unconnected-(U2-LINEOUT_L-Pad12)") (class "Default")
      (node (ref "U2") (pin "12") (pinfunction "LINEOUT_L_12") (pintype "bidirectional"))
    )
    (net (code "80") (name "unconnected-(U2-LINEOUT_R-Pad11)") (class "Default")
      (node (ref "U2") (pin "11") (pinfunction "LINEOUT_R_11") (pintype "bidirectional"))
    )
    (net (code "81") (name "unconnected-(U4-ADC0_DM0-Pad10)") (class "Default")
      (node (ref "U4") (pin "10") (pinfunction "ADC0_DM0_10") (pintype "bidirectional"))
    )
    (net (code "82") (name "unconnected-(U4-ADC0_DM3-Pad12)") (class "Default")
      (node (ref "U4") (pin "12") (pinfunction "ADC0_DM3_12") (pintype "bidirectional"))
    )
    (net (code "83") (name "unconnected-(U4-ADC0_DP0-Pad9)") (class "Default")
      (node (ref "U4") (pin "9") (pinfunction "ADC0_DP0_9") (pintype "bidirectional"))
    )
    (net (code "84") (name "unconnected-(U4-ADC0_DP3-Pad11)") (class "Default")
      (node (ref "U4") (pin "11") (pinfunction "ADC0_DP3_11") (pintype "bidirectional"))
    )
    (net (code "85") (name "unconnected-(U4-DAC0-Pad18)") (class "Default")
      (node (ref "U4") (pin "18") (pinfunction "DAC0_18") (pintype "bidirectional"))
    )
    (net (code "86") (name "unconnected-(U4-PTA4-Pad26)") (class "Default")
      (node (ref "U4") (pin "26") (pinfunction "PTA4_26") (pintype "bidirectional"))
    )
    (net (code "87") (name "unconnected-(U4-PTA5-Pad27)") (class "Default")
      (node (ref "U4") (pin "27") (pinfunction "PTA5_27") (pintype "bidirectional"))
    )
    (net (code "88") (name "unconnected-(U4-PTB1-Pad36)") (class "Default")
      (node (ref "U4") (pin "36") (pinfunction "PTB1_36") (pintype "bidirectional"))
    )
    (net (code "89") (name "unconnected-(U4-PTB16-Pad39)") (class "Default")
      (node (ref "U4") (pin "39") (pinfunction "PTB16_39") (pintype "bidirectional"))
    )
    (net (code "90") (name "unconnected-(U4-PTB17-Pad40)") (class "Default")
      (node (ref "U4") (pin "40") (pinfunction "PTB17_40") (pintype "bidirectional"))
    )
    (net (code "91") (name "unconnected-(U4-PTB18-Pad41)") (class "Default")
      (node (ref "U4") (pin "41") (pinfunction "PTB18_41") (pintype "bidirectional"))
    )
    (net (code "92") (name "unconnected-(U4-PTB19-Pad42)") (class "Default")
      (node (ref "U4") (pin "42") (pinfunction "PTB19_42") (pintype "bidirectional"))
    )
    (net (code "93") (name "unconnected-(U4-PTC7-Pad52)") (class "Default")
      (node (ref "U4") (pin "52") (pinfunction "PTC7_52") (pintype "bidirectional"))
    )
    (net (code "94") (name "unconnected-(U4-PTC8-Pad53)") (class "Default")
      (node (ref "U4") (pin "53") (pinfunction "PTC8_53") (pintype "bidirectional"))
    )
    (net (code "95") (name "unconnected-(U4-PTC9-Pad54)") (class "Default")
      (node (ref "U4") (pin "54") (pinfunction "PTC9_54") (pintype "bidirectional"))
    )
    (net (code "96") (name "unconnected-(U4-PTC10-Pad55)") (class "Default")
      (node (ref "U4") (pin "55") (pinfunction "PTC10_55") (pintype "bidirectional"))
    )
    (net (code "97") (name "unconnected-(U4-PTC11-Pad56)") (class "Default")
      (node (ref "U4") (pin "56") (pinfunction "PTC11_56") (pintype "bidirectional"))
    )
    (net (code "98") (name "unconnected-(U4-PTD0-Pad57)") (class "Default")
      (node (ref "U4") (pin "57") (pinfunction "PTD0_57") (pintype "bidirectional"))
    )
    (net (code "99") (name "unconnected-(U4-PTD1-Pad58)") (class "Default")
      (node (ref "U4") (pin "58") (pinfunction "PTD1_58") (pintype "bidirectional"))
    )
    (net (code "100") (name "unconnected-(U4-PTD2-Pad59)") (class "Default")
      (node (ref "U4") (pin "59") (pinfunction "PTD2_59") (pintype "bidirectional"))
    )
    (net (code "101") (name "unconnected-(U4-PTD3-Pad60)") (class "Default")
      (node (ref "U4") (pin "60") (pinfunction "PTD3_60") (pintype "bidirectional"))
    )
    (net (code "102") (name "unconnected-(U4-PTD4-Pad61)") (class "Default")
      (node (ref "U4") (pin "61") (pinfunction "PTD4_61") (pintype "bidirectional"))
    )
    (net (code "103") (name "unconnected-(U4-PTE0-Pad1)") (class "Default")
      (node (ref "U4") (pin "1") (pinfunction "PTE0_1") (pintype "bidirectional"))
    )
    (net (code "104") (name "unconnected-(U4-PTE1-Pad2)") (class "Default")
      (node (ref "U4") (pin "2") (pinfunction "PTE1_2") (pintype "bidirectional"))
    )
    (net (code "105") (name "unconnected-(U4-VREGIN-Pad8)") (class "Default")
      (node (ref "U4") (pin "8") (pinfunction "VREGIN_8") (pintype "bidirectional"))
    )
  )
)
